# PRJCTSheet.net
KiCad netlist of a schematic drawn in Altium Designer
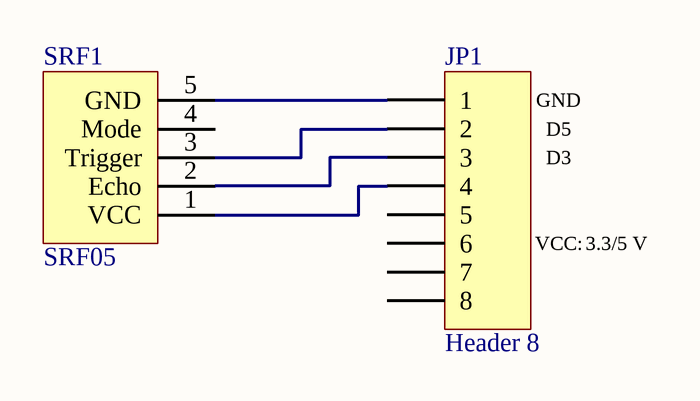
[diagram p0: PRJCTSheet.SchDoc]

(export (version "E")
  (design (tool "Eeschema 10.0.6"))
  (components
    (comp (ref "JP1")
      (value "Header 8")
      (footprint "HDR1X8")
      (description "Header, 8-Pin")
      (fields (field (name "PUBLISHER") "Altium Limited"))
      (libsource (lib "Miscellaneous Connectors") (part "Header 8"))
    )
    (comp (ref "SRF1")
      (value "SRF05")
      (footprint "SRF05")
      (description "SRF05 - Ultra-Sonic Ranger")
      (fields (field (name "DESIGNER") "Seyed Mohsen ghasemian"))
      (libsource (lib "PicPars.com_usefully_Library") (part "SRF05"))
    )
  )
  (nets
    (net (code "1") (name "Net-(SRF1-Echo)") (class "Default")
      (node (ref "JP1") (pin "3") (pinfunction "3_3") (pintype "passive"))
      (node (ref "SRF1") (pin "2") (pinfunction "Echo_2") (pintype "passive"))
    )
    (net (code "2") (name "Net-(SRF1-GND)") (class "Default")
      (node (ref "JP1") (pin "1") (pinfunction "1_1") (pintype "passive"))
      (node (ref "SRF1") (pin "5") (pinfunction "GND_5") (pintype "passive"))
    )
    (net (code "3") (name "Net-(SRF1-Trigger)") (class "Default")
      (node (ref "JP1") (pin "2") (pinfunction "2_2") (pintype "passive"))
      (node (ref "SRF1") (pin "3") (pinfunction "Trigger_3") (pintype "passive"))
    )
    (net (code "4") (name "Net-(SRF1-VCC)") (class "Default")
      (node (ref "JP1") (pin "4") (pinfunction "4_4") (pintype "passive"))
      (node (ref "SRF1") (pin "1") (pinfunction "VCC_1") (pintype "passive"))
    )
    (net (code "5") (name "unconnected-(JP1-Pad5)") (class "Default")
      (node (ref "JP1") (pin "5") (pinfunction "5_5") (pintype "passive"))
    )
    (net (code "6") (name "unconnected-(JP1-Pad6)") (class "Default")
      (node (ref "JP1") (pin "6") (pinfunction "6_6") (pintype "passive"))
    )
    (net (code "7") (name "unconnected-(JP1-Pad7)") (class "Default")
      (node (ref "JP1") (pin "7") (pinfunction "7_7") (pintype "passive"))
    )
    (net (code "8") (name "unconnected-(JP1-Pad8)") (class "Default")
      (node (ref "JP1") (pin "8") (pinfunction "8_8") (pintype "passive"))
    )
    (net (code "9") (name "unconnected-(SRF1-Mode-Pad4)") (class "Default")
      (node (ref "SRF1") (pin "4") (pinfunction "Mode_4") (pintype "passive"))
    )
  )
)
